# riser-extender-switch.net
KiCad netlist of a schematic drawn in EAGLE
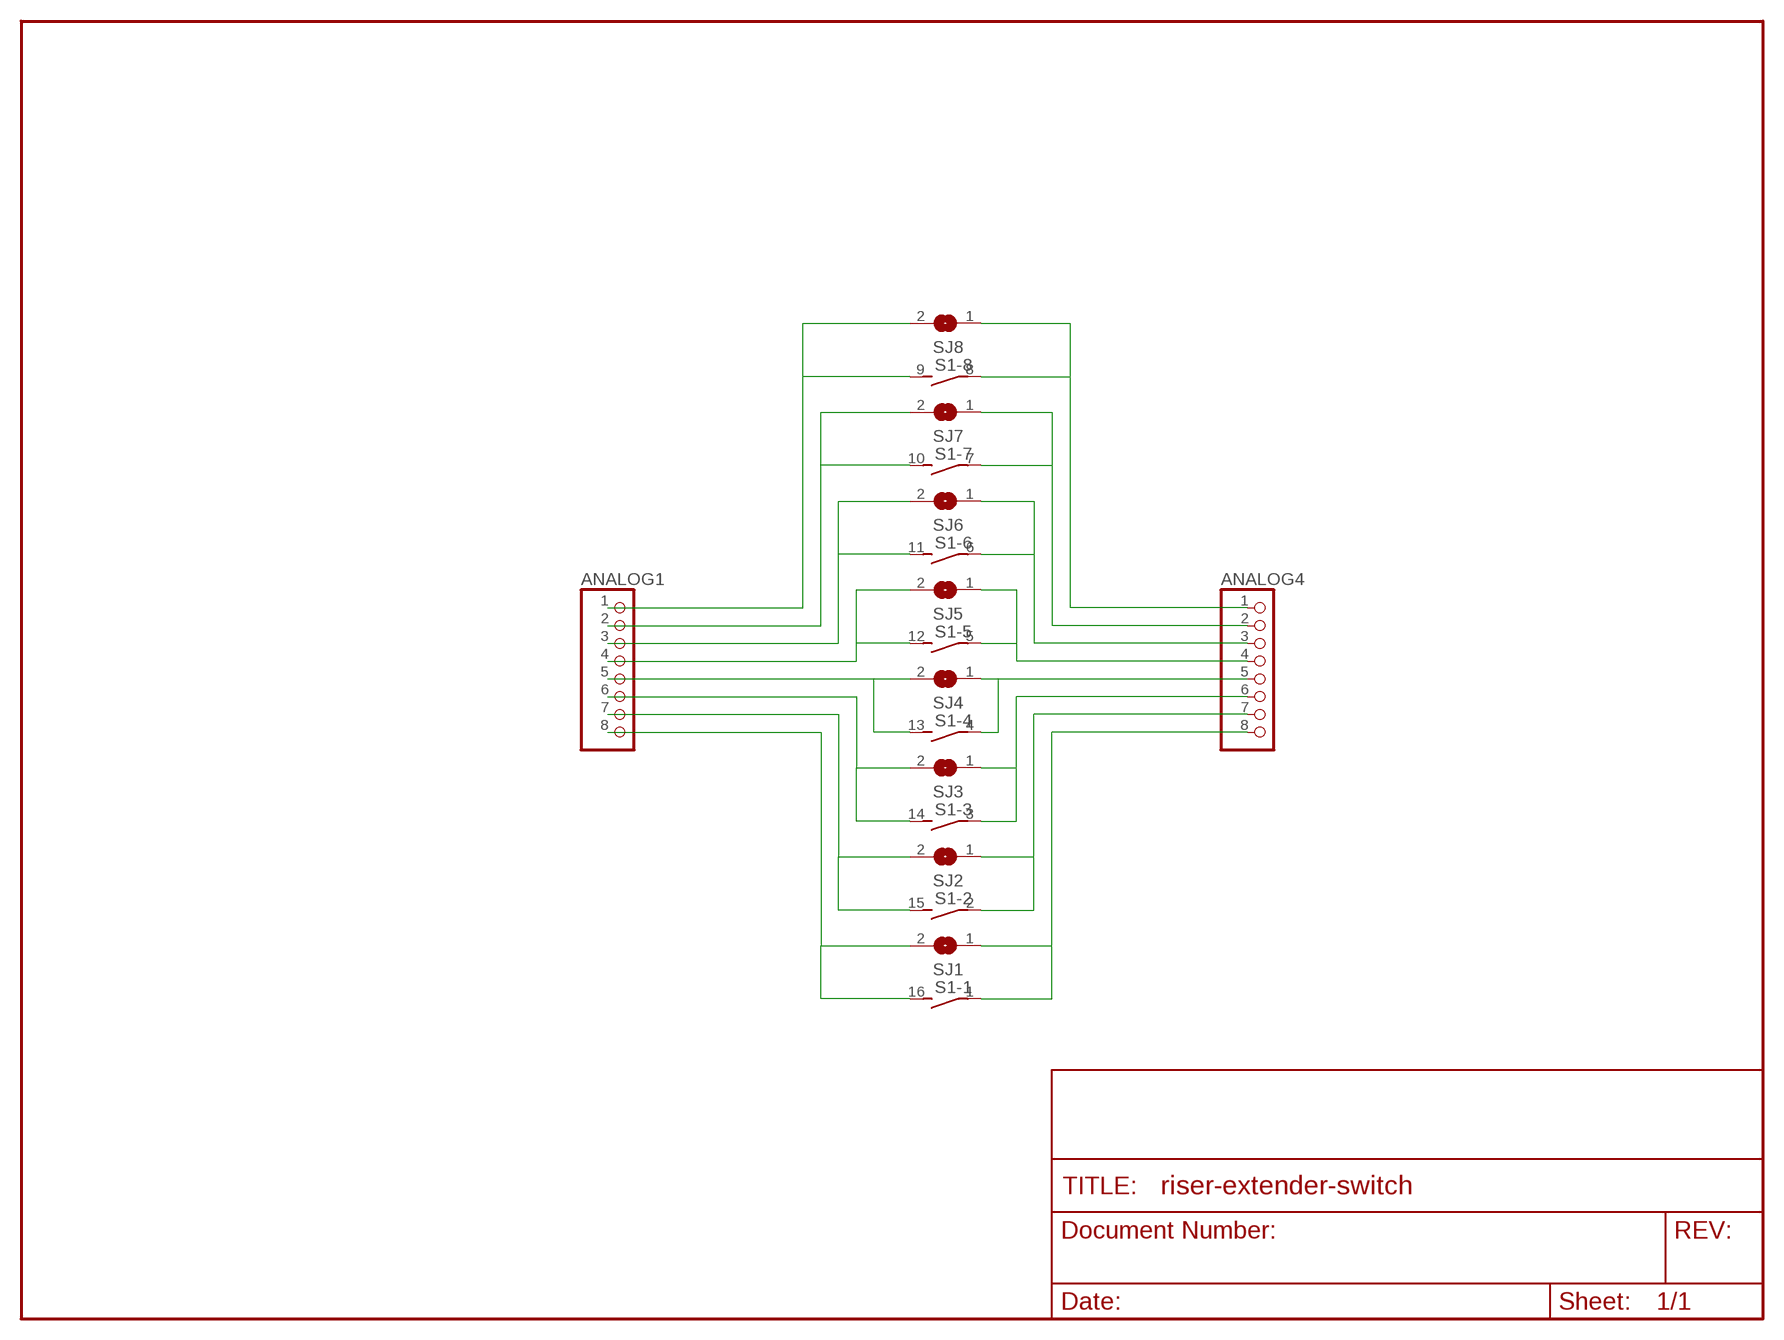
[diagram p0: schematic, sheet 1]

(export (version "E")
  (design (tool "Eeschema 10.0.6"))
  (components
    (comp (ref "ANALOG1")
      (value "PINHD-1X8")
      (footprint "eagle-import:1X08")
      (libsource (lib "eagle-import") (part "PINHD-1X8"))
    )
    (comp (ref "ANALOG4")
      (value "PINHD-1X8")
      (footprint "eagle-import:1X08")
      (libsource (lib "eagle-import") (part "PINHD-1X8"))
    )
    (comp (ref "S1")
      (value "DIP08S")
      (footprint "eagle-import:DIP08S")
      (libsource (lib "eagle-import") (part "DIP08S"))
    )
    (comp (ref "SJ1") (value "SJ") (footprint "eagle-import:SJ") (libsource (lib "eagle-import") (part "SJ")))
    (comp (ref "SJ2") (value "SJ") (footprint "eagle-import:SJ") (libsource (lib "eagle-import") (part "SJ")))
    (comp (ref "SJ3") (value "SJ") (footprint "eagle-import:SJ") (libsource (lib "eagle-import") (part "SJ")))
    (comp (ref "SJ4") (value "SJ") (footprint "eagle-import:SJ") (libsource (lib "eagle-import") (part "SJ")))
    (comp (ref "SJ5") (value "SJ") (footprint "eagle-import:SJ") (libsource (lib "eagle-import") (part "SJ")))
    (comp (ref "SJ6") (value "SJ") (footprint "eagle-import:SJ") (libsource (lib "eagle-import") (part "SJ")))
    (comp (ref "SJ7") (value "SJ") (footprint "eagle-import:SJ") (libsource (lib "eagle-import") (part "SJ")))
    (comp (ref "SJ8") (value "SJ") (footprint "eagle-import:SJ") (libsource (lib "eagle-import") (part "SJ")))
  )
  (nets
    (net (code "1") (name "Net-(ANALOG4-Pad8)") (class "Default")
      (node (ref "ANALOG4") (pin "8") (pinfunction "8_8") (pintype "passive"))
      (node (ref "S1") (pin "1") (pinfunction "1_1") (pintype "passive"))
      (node (ref "SJ1") (pin "1") (pinfunction "1_1") (pintype "passive"))
    )
    (net (code "2") (name "Net-(S1A-2)") (class "Default")
      (node (ref "ANALOG1") (pin "8") (pinfunction "8_8") (pintype "passive"))
      (node (ref "S1") (pin "16") (pinfunction "2_16") (pintype "passive"))
      (node (ref "SJ1") (pin "2") (pinfunction "2_2") (pintype "passive"))
    )
    (net (code "3") (name "Net-(S1B-1)") (class "Default")
      (node (ref "ANALOG4") (pin "7") (pinfunction "7_7") (pintype "passive"))
      (node (ref "S1") (pin "2") (pinfunction "1_2") (pintype "passive"))
      (node (ref "SJ2") (pin "1") (pinfunction "1_1") (pintype "passive"))
    )
    (net (code "4") (name "Net-(S1B-2)") (class "Default")
      (node (ref "ANALOG1") (pin "7") (pinfunction "7_7") (pintype "passive"))
      (node (ref "S1") (pin "15") (pinfunction "2_15") (pintype "passive"))
      (node (ref "SJ2") (pin "2") (pinfunction "2_2") (pintype "passive"))
    )
    (net (code "5") (name "Net-(S1C-1)") (class "Default")
      (node (ref "ANALOG4") (pin "6") (pinfunction "6_6") (pintype "passive"))
      (node (ref "S1") (pin "3") (pinfunction "1_3") (pintype "passive"))
      (node (ref "SJ3") (pin "1") (pinfunction "1_1") (pintype "passive"))
    )
    (net (code "6") (name "Net-(S1C-2)") (class "Default")
      (node (ref "ANALOG1") (pin "6") (pinfunction "6_6") (pintype "passive"))
      (node (ref "S1") (pin "14") (pinfunction "2_14") (pintype "passive"))
      (node (ref "SJ3") (pin "2") (pinfunction "2_2") (pintype "passive"))
    )
    (net (code "7") (name "Net-(S1D-1)") (class "Default")
      (node (ref "ANALOG4") (pin "5") (pinfunction "5_5") (pintype "passive"))
      (node (ref "S1") (pin "4") (pinfunction "1_4") (pintype "passive"))
      (node (ref "SJ4") (pin "1") (pinfunction "1_1") (pintype "passive"))
    )
    (net (code "8") (name "Net-(S1D-2)") (class "Default")
      (node (ref "ANALOG1") (pin "5") (pinfunction "5_5") (pintype "passive"))
      (node (ref "S1") (pin "13") (pinfunction "2_13") (pintype "passive"))
      (node (ref "SJ4") (pin "2") (pinfunction "2_2") (pintype "passive"))
    )
    (net (code "9") (name "Net-(S1E-1)") (class "Default")
      (node (ref "ANALOG4") (pin "4") (pinfunction "4_4") (pintype "passive"))
      (node (ref "S1") (pin "5") (pinfunction "1_5") (pintype "passive"))
      (node (ref "SJ5") (pin "1") (pinfunction "1_1") (pintype "passive"))
    )
    (net (code "10") (name "Net-(S1E-2)") (class "Default")
      (node (ref "ANALOG1") (pin "4") (pinfunction "4_4") (pintype "passive"))
      (node (ref "S1") (pin "12") (pinfunction "2_12") (pintype "passive"))
      (node (ref "SJ5") (pin "2") (pinfunction "2_2") (pintype "passive"))
    )
    (net (code "11") (name "Net-(S1F-1)") (class "Default")
      (node (ref "ANALOG4") (pin "3") (pinfunction "3_3") (pintype "passive"))
      (node (ref "S1") (pin "6") (pinfunction "1_6") (pintype "passive"))
      (node (ref "SJ6") (pin "1") (pinfunction "1_1") (pintype "passive"))
    )
    (net (code "12") (name "Net-(S1F-2)") (class "Default")
      (node (ref "ANALOG1") (pin "3") (pinfunction "3_3") (pintype "passive"))
      (node (ref "S1") (pin "11") (pinfunction "2_11") (pintype "passive"))
      (node (ref "SJ6") (pin "2") (pinfunction "2_2") (pintype "passive"))
    )
    (net (code "13") (name "Net-(S1G-1)") (class "Default")
      (node (ref "ANALOG4") (pin "2") (pinfunction "2_2") (pintype "passive"))
      (node (ref "S1") (pin "7") (pinfunction "1_7") (pintype "passive"))
      (node (ref "SJ7") (pin "1") (pinfunction "1_1") (pintype "passive"))
    )
    (net (code "14") (name "Net-(S1G-2)") (class "Default")
      (node (ref "ANALOG1") (pin "2") (pinfunction "2_2") (pintype "passive"))
      (node (ref "S1") (pin "10") (pinfunction "2_10") (pintype "passive"))
      (node (ref "SJ7") (pin "2") (pinfunction "2_2") (pintype "passive"))
    )
    (net (code "15") (name "Net-(S1H-1)") (class "Default")
      (node (ref "ANALOG4") (pin "1") (pinfunction "1_1") (pintype "passive"))
      (node (ref "S1") (pin "8") (pinfunction "1_8") (pintype "passive"))
      (node (ref "SJ8") (pin "1") (pinfunction "1_1") (pintype "passive"))
    )
    (net (code "16") (name "Net-(S1H-2)") (class "Default")
      (node (ref "ANALOG1") (pin "1") (pinfunction "1_1") (pintype "passive"))
      (node (ref "S1") (pin "9") (pinfunction "2_9") (pintype "passive"))
      (node (ref "SJ8") (pin "2") (pinfunction "2_2") (pintype "passive"))
    )
  )
)
